# UpTo11_FrontPanel.net
KiCad netlist of a schematic drawn in EAGLE
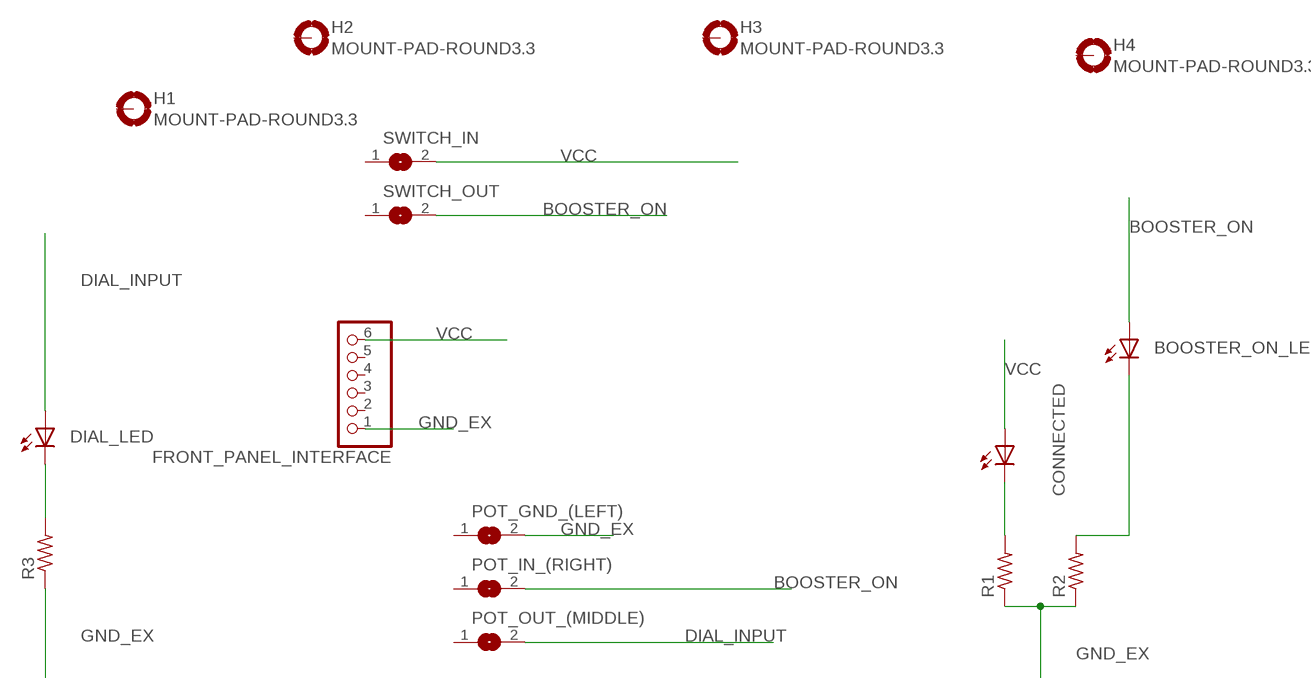
[diagram p0: schematic, sheet 1]

(export (version "E")
  (design (tool "Eeschema 10.0.6"))
  (components
    (comp (ref "BOOSTER_ON_LED")
      (value "LED5MM")
      (footprint "eagle-import:LED5MM")
      (libsource (lib "eagle-import") (part "LED5MM"))
    )
    (comp (ref "CONNECTED")
      (value "LEDSMT1206")
      (footprint "eagle-import:1206")
      (libsource (lib "eagle-import") (part "LEDSMT1206"))
    )
    (comp (ref "DIAL_LED")
      (value "LED5MM")
      (footprint "eagle-import:LED5MM")
      (libsource (lib "eagle-import") (part "LED5MM"))
    )
    (comp (ref "FRONT_PANEL_INTERFACE")
      (value "PINHD-1X6")
      (footprint "eagle-import:1X06")
      (libsource (lib "eagle-import") (part "PINHD-1X6"))
    )
    (comp (ref "H1")
      (value "MOUNT-PAD-ROUND3.3")
      (footprint "eagle-import:3,3-PAD")
      (libsource (lib "eagle-import") (part "MOUNT-PAD-ROUND3.3"))
    )
    (comp (ref "H2")
      (value "MOUNT-PAD-ROUND3.3")
      (footprint "eagle-import:3,3-PAD")
      (libsource (lib "eagle-import") (part "MOUNT-PAD-ROUND3.3"))
    )
    (comp (ref "H3")
      (value "MOUNT-PAD-ROUND3.3")
      (footprint "eagle-import:3,3-PAD")
      (libsource (lib "eagle-import") (part "MOUNT-PAD-ROUND3.3"))
    )
    (comp (ref "H4")
      (value "MOUNT-PAD-ROUND3.3")
      (footprint "eagle-import:3,3-PAD")
      (libsource (lib "eagle-import") (part "MOUNT-PAD-ROUND3.3"))
    )
    (comp (ref "POT_GND_(LEFT)")
      (value "SOLDERJUMPERREFLOW")
      (footprint "eagle-import:SOLDERJUMPER_REFLOW")
      (libsource (lib "eagle-import") (part "SOLDERJUMPERREFLOW"))
    )
    (comp (ref "POT_IN_(RIGHT)")
      (value "SOLDERJUMPERREFLOW")
      (footprint "eagle-import:SOLDERJUMPER_REFLOW")
      (libsource (lib "eagle-import") (part "SOLDERJUMPERREFLOW"))
    )
    (comp (ref "POT_OUT_(MIDDLE)")
      (value "SOLDERJUMPERREFLOW")
      (footprint "eagle-import:SOLDERJUMPER_REFLOW")
      (libsource (lib "eagle-import") (part "SOLDERJUMPERREFLOW"))
    )
    (comp (ref "R1")
      (value "R-US_R1206")
      (footprint "eagle-import:R1206")
      (libsource (lib "eagle-import") (part "R-US_R1206"))
    )
    (comp (ref "R2")
      (value "R-US_R1206")
      (footprint "eagle-import:R1206")
      (libsource (lib "eagle-import") (part "R-US_R1206"))
    )
    (comp (ref "R3")
      (value "R-US_R1206")
      (footprint "eagle-import:R1206")
      (libsource (lib "eagle-import") (part "R-US_R1206"))
    )
    (comp (ref "SWITCH_IN")
      (value "SOLDERJUMPERREFLOW")
      (footprint "eagle-import:SOLDERJUMPER_REFLOW")
      (libsource (lib "eagle-import") (part "SOLDERJUMPERREFLOW"))
    )
    (comp (ref "SWITCH_OUT")
      (value "SOLDERJUMPERREFLOW")
      (footprint "eagle-import:SOLDERJUMPER_REFLOW")
      (libsource (lib "eagle-import") (part "SOLDERJUMPERREFLOW"))
    )
  )
  (nets
    (net (code "1") (name "/BOOSTER_ON") (class "Default")
      (node (ref "BOOSTER_ON_LED") (pin "A") (pinfunction "A_A") (pintype "passive"))
      (node (ref "POT_IN_(RIGHT)") (pin "2") (pinfunction "2_2") (pintype "passive"))
      (node (ref "SWITCH_OUT") (pin "2") (pinfunction "2_2") (pintype "passive"))
    )
    (net (code "2") (name "/DIAL_INPUT") (class "Default")
      (node (ref "DIAL_LED") (pin "A") (pinfunction "A_A") (pintype "passive"))
      (node (ref "POT_OUT_(MIDDLE)") (pin "2") (pinfunction "2_2") (pintype "passive"))
    )
    (net (code "3") (name "/GND_EX") (class "Default")
      (node (ref "FRONT_PANEL_INTERFACE") (pin "1") (pinfunction "1_1") (pintype "passive"))
      (node (ref "POT_GND_(LEFT)") (pin "2") (pinfunction "2_2") (pintype "passive"))
      (node (ref "R1") (pin "1") (pinfunction "1_1") (pintype "passive"))
      (node (ref "R2") (pin "1") (pinfunction "1_1") (pintype "passive"))
      (node (ref "R3") (pin "1") (pinfunction "1_1") (pintype "passive"))
    )
    (net (code "4") (name "/VCC") (class "Default")
      (node (ref "CONNECTED") (pin "A") (pinfunction "A_A") (pintype "passive"))
      (node (ref "FRONT_PANEL_INTERFACE") (pin "6") (pinfunction "6_6") (pintype "passive"))
      (node (ref "SWITCH_IN") (pin "2") (pinfunction "2_2") (pintype "passive"))
    )
    (net (code "5") (name "Net-(BOOSTER_ON_LED-C)") (class "Default")
      (node (ref "BOOSTER_ON_LED") (pin "K") (pinfunction "C_K") (pintype "passive"))
      (node (ref "R2") (pin "2") (pinfunction "2_2") (pintype "passive"))
    )
    (net (code "6") (name "Net-(CONNECTED-PadC)") (class "Default")
      (node (ref "CONNECTED") (pin "C") (pinfunction "C_C") (pintype "passive"))
      (node (ref "R1") (pin "2") (pinfunction "2_2") (pintype "passive"))
    )
    (net (code "7") (name "Net-(DIAL_LED-C)") (class "Default")
      (node (ref "DIAL_LED") (pin "K") (pinfunction "C_K") (pintype "passive"))
      (node (ref "R3") (pin "2") (pinfunction "2_2") (pintype "passive"))
    )
    (net (code "8") (name "unconnected-(FRONT_PANEL_INTERFACE-Pad2)") (class "Default")
      (node (ref "FRONT_PANEL_INTERFACE") (pin "2") (pinfunction "2_2") (pintype "passive"))
    )
    (net (code "9") (name "unconnected-(FRONT_PANEL_INTERFACE-Pad3)") (class "Default")
      (node (ref "FRONT_PANEL_INTERFACE") (pin "3") (pinfunction "3_3") (pintype "passive"))
    )
    (net (code "10") (name "unconnected-(FRONT_PANEL_INTERFACE-Pad4)") (class "Default")
      (node (ref "FRONT_PANEL_INTERFACE") (pin "4") (pinfunction "4_4") (pintype "passive"))
    )
    (net (code "11") (name "unconnected-(FRONT_PANEL_INTERFACE-Pad5)") (class "Default")
      (node (ref "FRONT_PANEL_INTERFACE") (pin "5") (pinfunction "5_5") (pintype "passive"))
    )
    (net (code "12") (name "unconnected-(H1-MOUNT-PadB3,3)") (class "Default")
      (node (ref "H1") (pin "B3,3") (pinfunction "MOUNT_B3,3") (pintype "passive"))
    )
    (net (code "13") (name "unconnected-(H2-MOUNT-PadB3,3)") (class "Default")
      (node (ref "H2") (pin "B3,3") (pinfunction "MOUNT_B3,3") (pintype "passive"))
    )
    (net (code "14") (name "unconnected-(H3-MOUNT-PadB3,3)") (class "Default")
      (node (ref "H3") (pin "B3,3") (pinfunction "MOUNT_B3,3") (pintype "passive"))
    )
    (net (code "15") (name "unconnected-(H4-MOUNT-PadB3,3)") (class "Default")
      (node (ref "H4") (pin "B3,3") (pinfunction "MOUNT_B3,3") (pintype "passive"))
    )
    (net (code "16") (name "unconnected-(POT_GND_(LEFT)-Pad1)") (class "Default")
      (node (ref "POT_GND_(LEFT)") (pin "1") (pinfunction "1_1") (pintype "passive"))
    )
    (net (code "17") (name "unconnected-(POT_IN_(RIGHT)-Pad1)") (class "Default")
      (node (ref "POT_IN_(RIGHT)") (pin "1") (pinfunction "1_1") (pintype "passive"))
    )
    (net (code "18") (name "unconnected-(POT_OUT_(MIDDLE)-Pad1)") (class "Default")
      (node (ref "POT_OUT_(MIDDLE)") (pin "1") (pinfunction "1_1") (pintype "passive"))
    )
    (net (code "19") (name "unconnected-(SWITCH_IN-Pad1)") (class "Default")
      (node (ref "SWITCH_IN") (pin "1") (pinfunction "1_1") (pintype "passive"))
    )
    (net (code "20") (name "unconnected-(SWITCH_OUT-Pad1)") (class "Default")
      (node (ref "SWITCH_OUT") (pin "1") (pinfunction "1_1") (pintype "passive"))
    )
  )
)
